# main.net
KiCad netlist of a schematic drawn in EAGLE
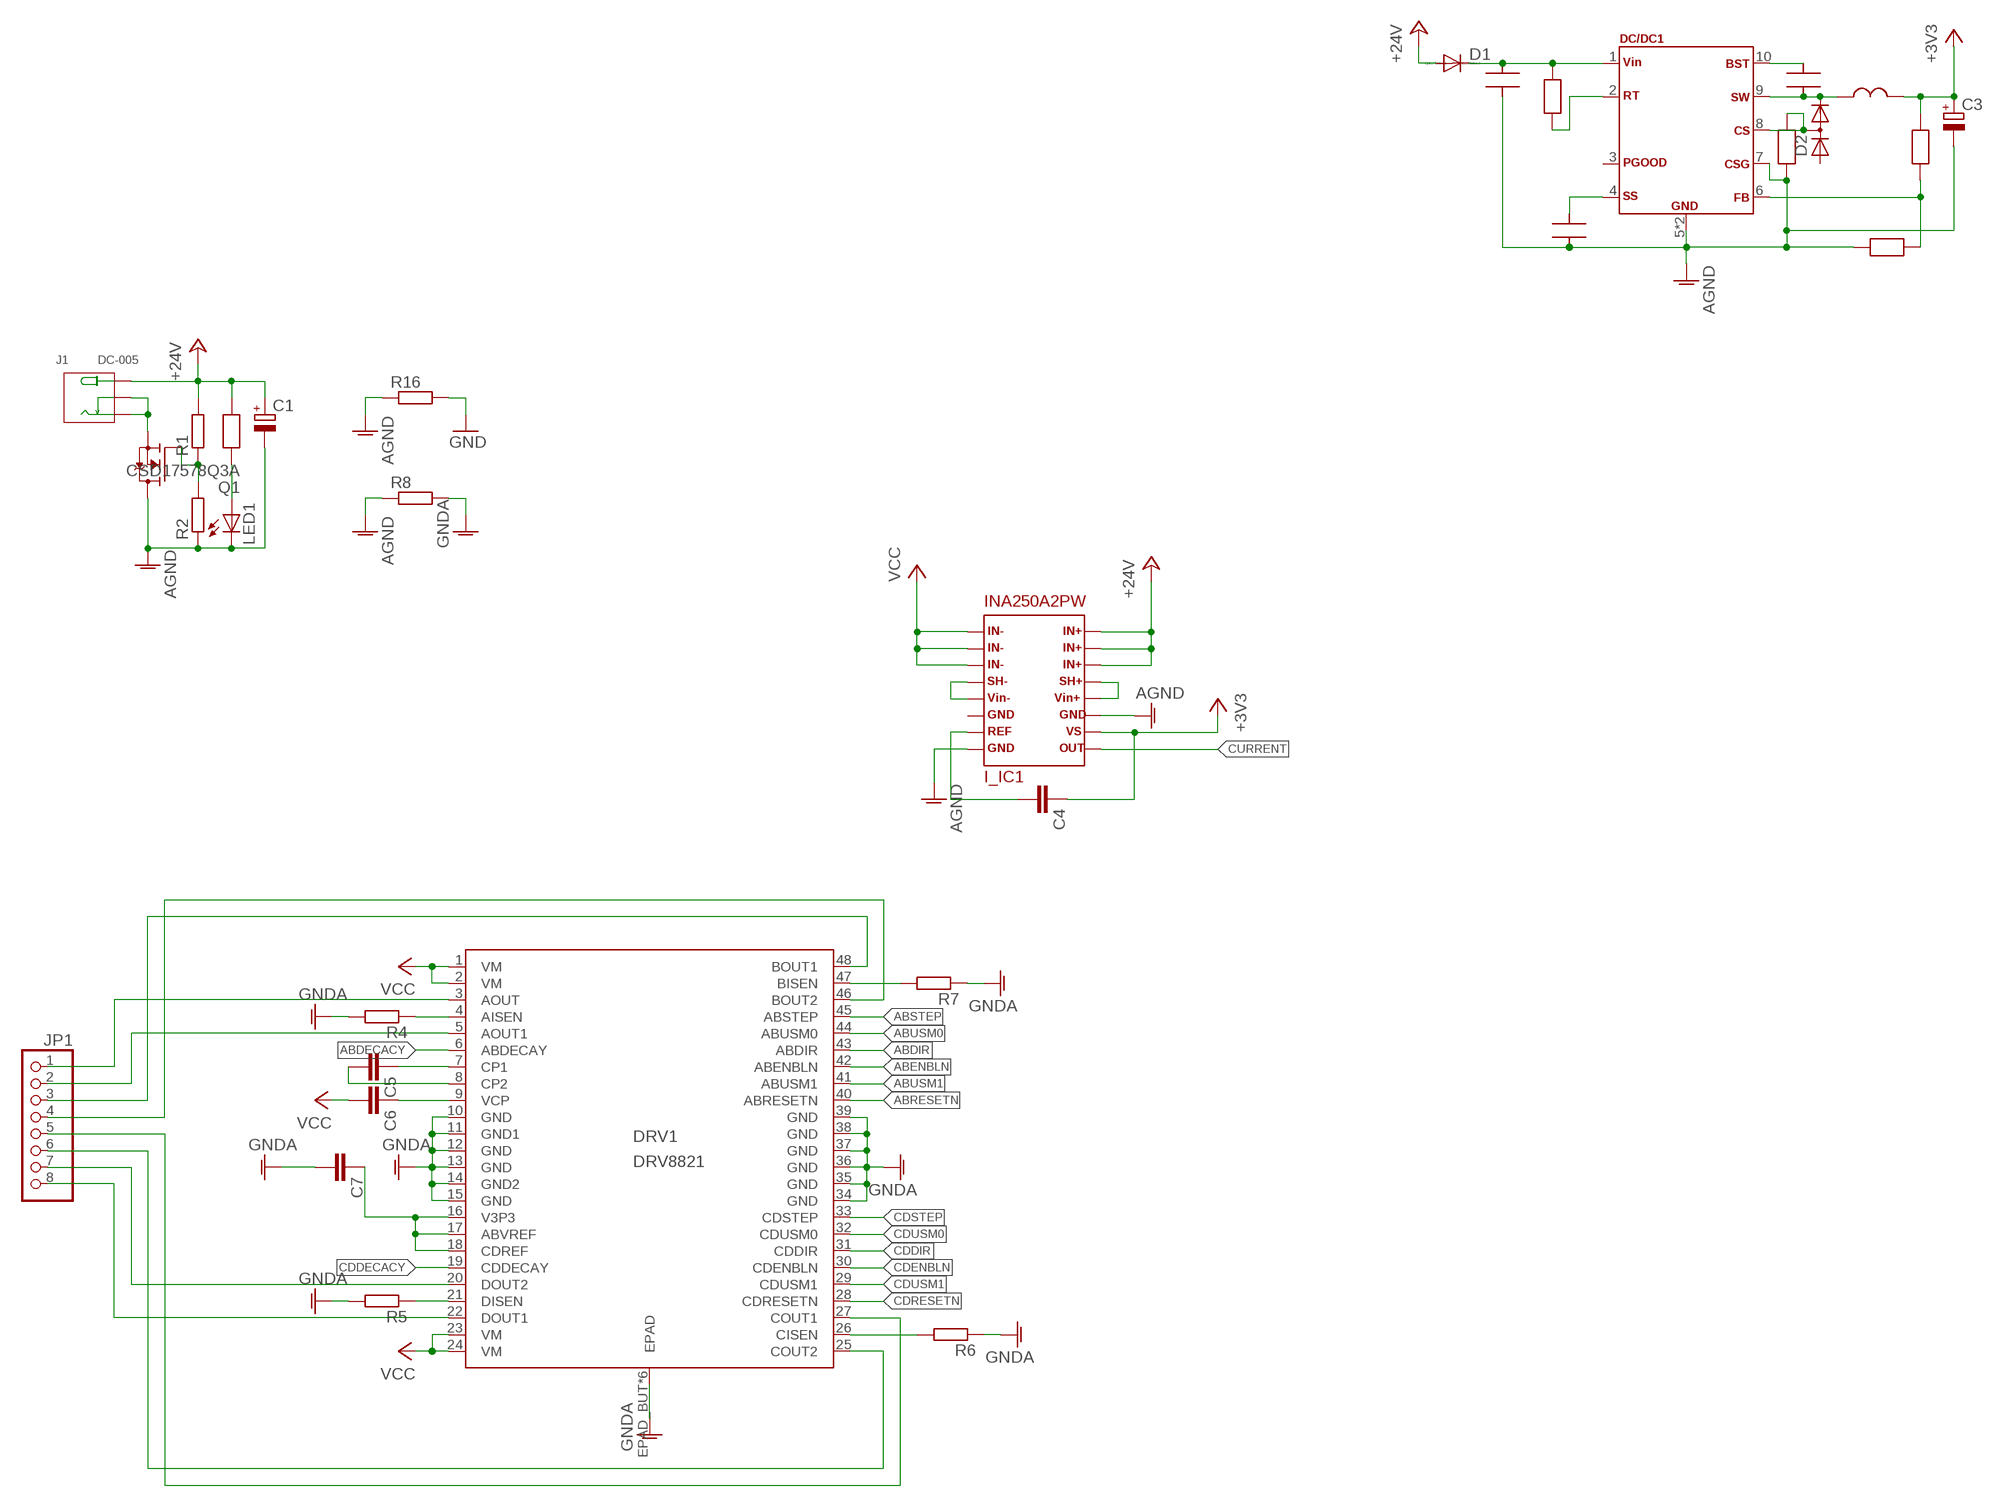
[diagram p0: schematic, sheet 1, part 1 of 2]
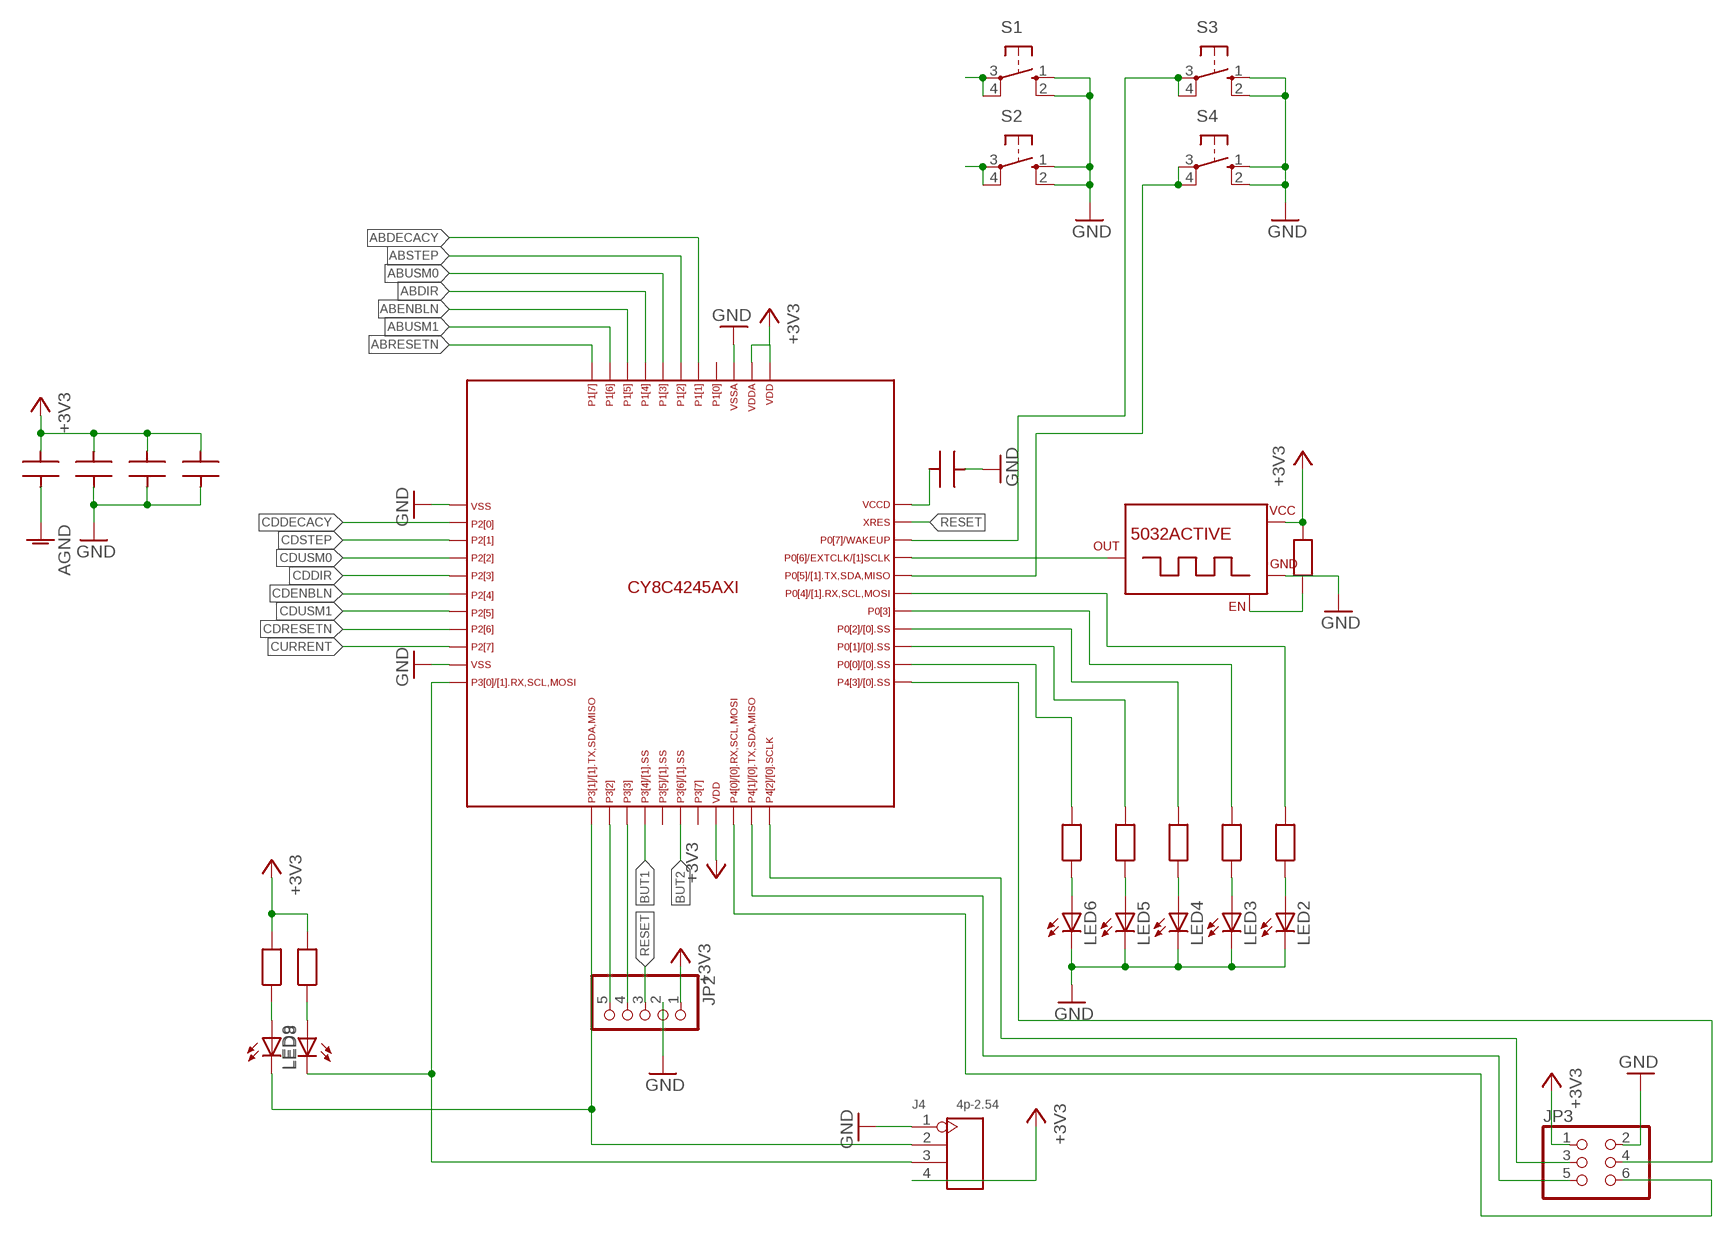
[diagram p1: schematic, sheet 1, part 2 of 2]

(export (version "E")
  (design (tool "Eeschema 10.0.6"))
  (components
    (comp (ref "C1")
      (value "CPOL-EUSMCD")
      (footprint "eagle-import:SMC_D")
      (libsource (lib "eagle-import") (part "CPOL-EUSMCD"))
    )
    (comp (ref "C2")
      (value "CAP0603")
      (footprint "eagle-import:C0603")
      (libsource (lib "eagle-import") (part "CAP0603"))
    )
    (comp (ref "C3")
      (value "CPOL-EUSMCD")
      (footprint "eagle-import:SMC_D")
      (libsource (lib "eagle-import") (part "CPOL-EUSMCD"))
    )
    (comp (ref "C4")
      (value "C-EUC0805")
      (footprint "eagle-import:C0805")
      (libsource (lib "eagle-import") (part "C-EUC0805"))
    )
    (comp (ref "C5")
      (value "C-EUC0805")
      (footprint "eagle-import:C0805")
      (libsource (lib "eagle-import") (part "C-EUC0805"))
    )
    (comp (ref "C6")
      (value "C-EUC0805")
      (footprint "eagle-import:C0805")
      (libsource (lib "eagle-import") (part "C-EUC0805"))
    )
    (comp (ref "C7")
      (value "C-EUC0805")
      (footprint "eagle-import:C0805")
      (libsource (lib "eagle-import") (part "C-EUC0805"))
    )
    (comp (ref "C8")
      (value "CAP0603")
      (footprint "eagle-import:C0603")
      (libsource (lib "eagle-import") (part "CAP0603"))
    )
    (comp (ref "C9")
      (value "CAP0603")
      (footprint "eagle-import:C0603")
      (libsource (lib "eagle-import") (part "CAP0603"))
    )
    (comp (ref "C10")
      (value "CAP0603")
      (footprint "eagle-import:C0603")
      (libsource (lib "eagle-import") (part "CAP0603"))
    )
    (comp (ref "C11")
      (value "CAP0603")
      (footprint "eagle-import:C0603")
      (libsource (lib "eagle-import") (part "CAP0603"))
    )
    (comp (ref "C12")
      (value "CAP0603")
      (footprint "eagle-import:C0603")
      (libsource (lib "eagle-import") (part "CAP0603"))
    )
    (comp (ref "C13")
      (value "CAP0603")
      (footprint "eagle-import:C0603")
      (libsource (lib "eagle-import") (part "CAP0603"))
    )
    (comp (ref "C14")
      (value "CAP0603")
      (footprint "eagle-import:C0603")
      (libsource (lib "eagle-import") (part "CAP0603"))
    )
    (comp (ref "D1")
      (value "DIODE-DO-214AC")
      (footprint "eagle-import:DO-214AC")
      (libsource (lib "eagle-import") (part "DIODE-DO-214AC"))
    )
    (comp (ref "D2")
      (value "DIODE_2CACA-SOT23")
      (footprint "eagle-import:SOT23")
      (libsource (lib "eagle-import") (part "DIODE_2CACA-SOT23"))
    )
    (comp (ref "DC/DC1")
      (value "LM25011")
      (footprint "eagle-import:HVSSOP-10")
      (libsource (lib "eagle-import") (part "LM25011"))
    )
    (comp (ref "DRV1")
      (value "DRV8821")
      (footprint "eagle-import:HTSSOP_48")
      (libsource (lib "eagle-import") (part "DRV8821"))
    )
    (comp (ref "I_IC1")
      (value "INA250A2PW")
      (footprint "eagle-import:SSOP16")
      (libsource (lib "eagle-import") (part "INA250A2PW"))
    )
    (comp (ref "J1")
      (value "DC-005")
      (footprint "eagle-import:DCJ3P-14.2X11.0X9.0MM")
      (libsource (lib "eagle-import") (part "CONN-POWER-JACK-2.1MM(DC-005)"))
    )
    (comp (ref "J4")
      (value "4p-2.54")
      (footprint "eagle-import:H4-2.54")
      (fields (field (name "MPN") "F185-1104A1BSYA1"))
      (libsource (lib "eagle-import") (part "DIP-BLACK-FEMALE-HEADER-VERT(4P-2.54)"))
    )
    (comp (ref "JP1")
      (value "PINHD-1X8")
      (footprint "eagle-import:1X08")
      (libsource (lib "eagle-import") (part "PINHD-1X8"))
    )
    (comp (ref "JP2")
      (value "PINHD-1X5")
      (footprint "eagle-import:1X05")
      (libsource (lib "eagle-import") (part "PINHD-1X5"))
    )
    (comp (ref "JP3")
      (value "PINHD-2X3")
      (footprint "eagle-import:2X03")
      (libsource (lib "eagle-import") (part "PINHD-2X3"))
    )
    (comp (ref "L1")
      (value "L0603")
      (footprint "eagle-import:L0603")
      (libsource (lib "eagle-import") (part "L0603"))
    )
    (comp (ref "LED1")
      (value "LEDCHIP-LED0805")
      (footprint "eagle-import:CHIP-LED0805")
      (libsource (lib "eagle-import") (part "LEDCHIP-LED0805"))
    )
    (comp (ref "LED2")
      (value "LEDCHIP-LED0603")
      (footprint "eagle-import:CHIP-LED0603")
      (libsource (lib "eagle-import") (part "LEDCHIP-LED0603"))
    )
    (comp (ref "LED3")
      (value "LEDCHIP-LED0603")
      (footprint "eagle-import:CHIP-LED0603")
      (libsource (lib "eagle-import") (part "LEDCHIP-LED0603"))
    )
    (comp (ref "LED4")
      (value "LEDCHIP-LED0603")
      (footprint "eagle-import:CHIP-LED0603")
      (libsource (lib "eagle-import") (part "LEDCHIP-LED0603"))
    )
    (comp (ref "LED5")
      (value "LEDCHIP-LED0603")
      (footprint "eagle-import:CHIP-LED0603")
      (libsource (lib "eagle-import") (part "LEDCHIP-LED0603"))
    )
    (comp (ref "LED6")
      (value "LEDCHIP-LED0603")
      (footprint "eagle-import:CHIP-LED0603")
      (libsource (lib "eagle-import") (part "LEDCHIP-LED0603"))
    )
    (comp (ref "LED8")
      (value "LEDCHIP-LED0603")
      (footprint "eagle-import:CHIP-LED0603")
      (libsource (lib "eagle-import") (part "LEDCHIP-LED0603"))
    )
    (comp (ref "LED9")
      (value "LEDCHIP-LED0603")
      (footprint "eagle-import:CHIP-LED0603")
      (libsource (lib "eagle-import") (part "LEDCHIP-LED0603"))
    )
    (comp (ref "Q1")
      (value "CSD17578Q3A")
      (footprint "eagle-import:VSONP8")
      (libsource (lib "eagle-import") (part "CSD17578Q3A"))
    )
    (comp (ref "R1")
      (value "R-EU_M0805")
      (footprint "eagle-import:M0805")
      (libsource (lib "eagle-import") (part "R-EU_M0805"))
    )
    (comp (ref "R2")
      (value "R-EU_M0805")
      (footprint "eagle-import:M0805")
      (libsource (lib "eagle-import") (part "R-EU_M0805"))
    )
    (comp (ref "R3")
      (value "RES0603")
      (footprint "eagle-import:R0603")
      (libsource (lib "eagle-import") (part "RES0603"))
    )
    (comp (ref "R4")
      (value "R-EU_M0805")
      (footprint "eagle-import:M0805")
      (libsource (lib "eagle-import") (part "R-EU_M0805"))
    )
    (comp (ref "R5")
      (value "R-EU_M0805")
      (footprint "eagle-import:M0805")
      (libsource (lib "eagle-import") (part "R-EU_M0805"))
    )
    (comp (ref "R6")
      (value "R-EU_M0805")
      (footprint "eagle-import:M0805")
      (libsource (lib "eagle-import") (part "R-EU_M0805"))
    )
    (comp (ref "R7")
      (value "R-EU_M0805")
      (footprint "eagle-import:M0805")
      (libsource (lib "eagle-import") (part "R-EU_M0805"))
    )
    (comp (ref "R8")
      (value "R-EU_M0805")
      (footprint "eagle-import:M0805")
      (libsource (lib "eagle-import") (part "R-EU_M0805"))
    )
    (comp (ref "R9")
      (value "RES0603")
      (footprint "eagle-import:R0603")
      (libsource (lib "eagle-import") (part "RES0603"))
    )
    (comp (ref "R10")
      (value "RES0603")
      (footprint "eagle-import:R0603")
      (libsource (lib "eagle-import") (part "RES0603"))
    )
    (comp (ref "R11")
      (value "RES0603")
      (footprint "eagle-import:R0603")
      (libsource (lib "eagle-import") (part "RES0603"))
    )
    (comp (ref "R12")
      (value "RES0603")
      (footprint "eagle-import:R0603")
      (libsource (lib "eagle-import") (part "RES0603"))
    )
    (comp (ref "R13")
      (value "RES0603")
      (footprint "eagle-import:R0603")
      (libsource (lib "eagle-import") (part "RES0603"))
    )
    (comp (ref "R14")
      (value "RES0603")
      (footprint "eagle-import:R0603")
      (libsource (lib "eagle-import") (part "RES0603"))
    )
    (comp (ref "R15")
      (value "RES0603")
      (footprint "eagle-import:R0603")
      (libsource (lib "eagle-import") (part "RES0603"))
    )
    (comp (ref "R16")
      (value "R-EU_M0805")
      (footprint "eagle-import:M0805")
      (libsource (lib "eagle-import") (part "R-EU_M0805"))
    )
    (comp (ref "R17")
      (value "RES0603")
      (footprint "eagle-import:R0603")
      (libsource (lib "eagle-import") (part "RES0603"))
    )
    (comp (ref "R18")
      (value "RES0603")
      (footprint "eagle-import:R0603")
      (libsource (lib "eagle-import") (part "RES0603"))
    )
    (comp (ref "R19")
      (value "RES0603")
      (footprint "eagle-import:R0603")
      (libsource (lib "eagle-import") (part "RES0603"))
    )
    (comp (ref "R20")
      (value "RES0603")
      (footprint "eagle-import:R0603")
      (libsource (lib "eagle-import") (part "RES0603"))
    )
    (comp (ref "R21")
      (value "RES0603")
      (footprint "eagle-import:R0603")
      (libsource (lib "eagle-import") (part "RES0603"))
    )
    (comp (ref "S1")
      (value "10-XX")
      (footprint "eagle-import:B3F-10XX")
      (fields (field (name "MPN") "B3F-1000"))
      (libsource (lib "eagle-import") (part "10-XX"))
    )
    (comp (ref "S2")
      (value "10-XX")
      (footprint "eagle-import:B3F-10XX")
      (fields (field (name "MPN") "B3F-1000"))
      (libsource (lib "eagle-import") (part "10-XX"))
    )
    (comp (ref "S3")
      (value "10-XX")
      (footprint "eagle-import:B3F-10XX")
      (fields (field (name "MPN") "B3F-1000"))
      (libsource (lib "eagle-import") (part "10-XX"))
    )
    (comp (ref "S4")
      (value "10-XX")
      (footprint "eagle-import:B3F-10XX")
      (fields (field (name "MPN") "B3F-1000"))
      (libsource (lib "eagle-import") (part "10-XX"))
    )
    (comp (ref "U$1")
      (value "CY8C4245")
      (footprint "eagle-import:TQFP44_CY_LOGO")
      (libsource (lib "eagle-import") (part "CY8C4245"))
    )
    (comp (ref "U$4")
      (value "5032ACTIVE")
      (footprint "eagle-import:5030A")
      (libsource (lib "eagle-import") (part "5032ACTIVE"))
    )
  )
  (nets
    (net (code "1") (name "+3V3") (class "Default")
      (node (ref "C10") (pin "1") (pinfunction "P$1_1") (pintype "bidirectional"))
      (node (ref "C12") (pin "1") (pinfunction "P$1_1") (pintype "bidirectional"))
      (node (ref "C13") (pin "1") (pinfunction "P$1_1") (pintype "bidirectional"))
      (node (ref "C14") (pin "1") (pinfunction "P$1_1") (pintype "bidirectional"))
      (node (ref "C3") (pin "+") (pinfunction "+_+") (pintype "passive"))
      (node (ref "C4") (pin "1") (pinfunction "1_1") (pintype "passive"))
      (node (ref "I_IC1") (pin "P$10") (pinfunction "P$10_P$10") (pintype "bidirectional"))
      (node (ref "J4") (pin "4") (pinfunction "P$4_4") (pintype "bidirectional"))
      (node (ref "JP2") (pin "1") (pinfunction "1_1") (pintype "passive"))
      (node (ref "JP3") (pin "1") (pinfunction "1_1") (pintype "passive"))
      (node (ref "L1") (pin "2") (pinfunction "P$2_2") (pintype "bidirectional"))
      (node (ref "R14") (pin "2") (pinfunction "P$2_2") (pintype "bidirectional"))
      (node (ref "R15") (pin "2") (pinfunction "P$2_2") (pintype "bidirectional"))
      (node (ref "R17") (pin "1") (pinfunction "P$1_1") (pintype "bidirectional"))
      (node (ref "R21") (pin "1") (pinfunction "P$1_1") (pintype "bidirectional"))
      (node (ref "U$1") (pin "19") (pinfunction "19_19") (pintype "bidirectional"))
      (node (ref "U$1") (pin "34") (pinfunction "34_34") (pintype "bidirectional"))
      (node (ref "U$1") (pin "35") (pinfunction "35_35") (pintype "bidirectional"))
      (node (ref "U$4") (pin "4") (pinfunction "+5V_4") (pintype "bidirectional"))
    )
    (net (code "2") (name "+24V") (class "Default")
      (node (ref "C1") (pin "+") (pinfunction "+_+") (pintype "passive"))
      (node (ref "D1") (pin "A") (pinfunction "A_A") (pintype "passive"))
      (node (ref "I_IC1") (pin "P$14") (pinfunction "P$14_P$14") (pintype "bidirectional"))
      (node (ref "I_IC1") (pin "P$15") (pinfunction "P$15_P$15") (pintype "bidirectional"))
      (node (ref "I_IC1") (pin "P$16") (pinfunction "P$16_P$16") (pintype "bidirectional"))
      (node (ref "J1") (pin "+") (pinfunction "+_+") (pintype "bidirectional"))
      (node (ref "R1") (pin "2") (pinfunction "2_2") (pintype "passive"))
      (node (ref "R3") (pin "2") (pinfunction "P$2_2") (pintype "bidirectional"))
    )
    (net (code "3") (name "ABDECACY") (class "Default")
      (node (ref "DRV1") (pin "6") (pinfunction "ABDECAY_6") (pintype "bidirectional"))
      (node (ref "U$1") (pin "38") (pinfunction "38_38") (pintype "bidirectional"))
    )
    (net (code "4") (name "ABDIR") (class "Default")
      (node (ref "DRV1") (pin "43") (pinfunction "ABDIR_43") (pintype "input"))
      (node (ref "U$1") (pin "41") (pinfunction "41_41") (pintype "bidirectional"))
    )
    (net (code "5") (name "ABENBLN") (class "Default")
      (node (ref "DRV1") (pin "42") (pinfunction "ABENBLN_42") (pintype "input"))
      (node (ref "U$1") (pin "42") (pinfunction "42_42") (pintype "bidirectional"))
    )
    (net (code "6") (name "ABRESETN") (class "Default")
      (node (ref "DRV1") (pin "40") (pinfunction "ABRESETN_40") (pintype "input"))
      (node (ref "U$1") (pin "44") (pinfunction "44_44") (pintype "bidirectional"))
    )
    (net (code "7") (name "ABSTEP") (class "Default")
      (node (ref "DRV1") (pin "45") (pinfunction "ABSTEP_45") (pintype "input"))
      (node (ref "U$1") (pin "39") (pinfunction "39_39") (pintype "bidirectional"))
    )
    (net (code "8") (name "ABUSM0") (class "Default")
      (node (ref "DRV1") (pin "44") (pinfunction "ABUSM0_44") (pintype "input"))
      (node (ref "U$1") (pin "40") (pinfunction "40_40") (pintype "bidirectional"))
    )
    (net (code "9") (name "ABUSM1") (class "Default")
      (node (ref "DRV1") (pin "41") (pinfunction "ABUSM1_41") (pintype "input"))
      (node (ref "U$1") (pin "43") (pinfunction "43_43") (pintype "bidirectional"))
    )
    (net (code "10") (name "AGND") (class "Default")
      (node (ref "C1") (pin "-") (pinfunction "-_-") (pintype "passive"))
      (node (ref "C14") (pin "2") (pinfunction "P$2_2") (pintype "bidirectional"))
      (node (ref "C2") (pin "1") (pinfunction "P$1_1") (pintype "bidirectional"))
      (node (ref "C3") (pin "-") (pinfunction "-_-") (pintype "passive"))
      (node (ref "C8") (pin "1") (pinfunction "P$1_1") (pintype "bidirectional"))
      (node (ref "DC/DC1") (pin "5") (pinfunction "5_5") (pintype "bidirectional"))
      (node (ref "DC/DC1") (pin "7") (pinfunction "7_7") (pintype "bidirectional"))
      (node (ref "DC/DC1") (pin "EPAD") (pinfunction "5_EPAD") (pintype "bidirectional"))
      (node (ref "I_IC1") (pin "P$11") (pinfunction "P$11_P$11") (pintype "bidirectional"))
      (node (ref "I_IC1") (pin "P$8") (pinfunction "P$8_P$8") (pintype "bidirectional"))
      (node (ref "LED1") (pin "C") (pinfunction "C_C") (pintype "passive"))
      (node (ref "Q1") (pin "D1") (pinfunction "D_D1") (pintype "passive"))
      (node (ref "Q1") (pin "D2") (pinfunction "D_D2") (pintype "passive"))
      (node (ref "Q1") (pin "D3") (pinfunction "D_D3") (pintype "passive"))
      (node (ref "Q1") (pin "D4") (pinfunction "D_D4") (pintype "passive"))
      (node (ref "Q1") (pin "D5") (pinfunction "D_D5") (pintype "passive"))
      (node (ref "R16") (pin "1") (pinfunction "1_1") (pintype "passive"))
      (node (ref "R19") (pin "1") (pinfunction "P$1_1") (pintype "bidirectional"))
      (node (ref "R2") (pin "1") (pinfunction "1_1") (pintype "passive"))
      (node (ref "R20") (pin "2") (pinfunction "P$2_2") (pintype "bidirectional"))
      (node (ref "R8") (pin "1") (pinfunction "1_1") (pintype "passive"))
    )
    (net (code "11") (name "BUT1") (class "Default")
      (node (ref "S1") (pin "3") (pinfunction "P_3") (pintype "passive"))
      (node (ref "S1") (pin "4") (pinfunction "P1_4") (pintype "passive"))
      (node (ref "U$1") (pin "15") (pinfunction "15_15") (pintype "bidirectional"))
    )
    (net (code "12") (name "BUT2") (class "Default")
      (node (ref "S2") (pin "3") (pinfunction "P_3") (pintype "passive"))
      (node (ref "S2") (pin "4") (pinfunction "P1_4") (pintype "passive"))
      (node (ref "U$1") (pin "17") (pinfunction "17_17") (pintype "bidirectional"))
    )
    (net (code "13") (name "CDDECACY") (class "Default")
      (node (ref "DRV1") (pin "19") (pinfunction "CDDECAY_19") (pintype "input"))
      (node (ref "U$1") (pin "2") (pinfunction "2_2") (pintype "bidirectional"))
    )
    (net (code "14") (name "CDDIR") (class "Default")
      (node (ref "DRV1") (pin "31") (pinfunction "CDDIR_31") (pintype "input"))
      (node (ref "U$1") (pin "5") (pinfunction "5_5") (pintype "bidirectional"))
    )
    (net (code "15") (name "CDENBLN") (class "Default")
      (node (ref "DRV1") (pin "30") (pinfunction "CDENBLN_30") (pintype "input"))
      (node (ref "U$1") (pin "6") (pinfunction "6_6") (pintype "bidirectional"))
    )
    (net (code "16") (name "CDRESETN") (class "Default")
      (node (ref "DRV1") (pin "28") (pinfunction "CDRESETN_28") (pintype "input"))
      (node (ref "U$1") (pin "8") (pinfunction "8_8") (pintype "bidirectional"))
    )
    (net (code "17") (name "CDSTEP") (class "Default")
      (node (ref "DRV1") (pin "33") (pinfunction "CDSTEP_33") (pintype "input"))
      (node (ref "U$1") (pin "3") (pinfunction "3_3") (pintype "bidirectional"))
    )
    (net (code "18") (name "CDUSM0") (class "Default")
      (node (ref "DRV1") (pin "32") (pinfunction "CDUSM0_32") (pintype "input"))
      (node (ref "U$1") (pin "4") (pinfunction "4_4") (pintype "bidirectional"))
    )
    (net (code "19") (name "CDUSM1") (class "Default")
      (node (ref "DRV1") (pin "29") (pinfunction "CDUSM1_29") (pintype "input"))
      (node (ref "U$1") (pin "7") (pinfunction "7_7") (pintype "bidirectional"))
    )
    (net (code "20") (name "CURRENT") (class "Default")
      (node (ref "I_IC1") (pin "P$9") (pinfunction "P$9_P$9") (pintype "bidirectional"))
      (node (ref "U$1") (pin "9") (pinfunction "9_9") (pintype "bidirectional"))
    )
    (net (code "21") (name "GND") (class "Default")
      (node (ref "C10") (pin "2") (pinfunction "P$2_2") (pintype "bidirectional"))
      (node (ref "C11") (pin "1") (pinfunction "P$1_1") (pintype "bidirectional"))
      (node (ref "C12") (pin "2") (pinfunction "P$2_2") (pintype "bidirectional"))
      (node (ref "C13") (pin "2") (pinfunction "P$2_2") (pintype "bidirectional"))
      (node (ref "J4") (pin "1") (pinfunction "P$1_1") (pintype "bidirectional"))
      (node (ref "JP2") (pin "2") (pinfunction "2_2") (pintype "passive"))
      (node (ref "JP3") (pin "2") (pinfunction "2_2") (pintype "passive"))
      (node (ref "LED2") (pin "C") (pinfunction "C_C") (pintype "passive"))
      (node (ref "LED3") (pin "C") (pinfunction "C_C") (pintype "passive"))
      (node (ref "LED4") (pin "C") (pinfunction "C_C") (pintype "passive"))
      (node (ref "LED5") (pin "C") (pinfunction "C_C") (pintype "passive"))
      (node (ref "LED6") (pin "C") (pinfunction "C_C") (pintype "passive"))
      (node (ref "R16") (pin "2") (pinfunction "2_2") (pintype "passive"))
      (node (ref "S1") (pin "1") (pinfunction "S_1") (pintype "passive"))
      (node (ref "S1") (pin "2") (pinfunction "S1_2") (pintype "passive"))
      (node (ref "S2") (pin "1") (pinfunction "S_1") (pintype "passive"))
      (node (ref "S2") (pin "2") (pinfunction "S1_2") (pintype "passive"))
      (node (ref "S3") (pin "1") (pinfunction "S_1") (pintype "passive"))
      (node (ref "S3") (pin "2") (pinfunction "S1_2") (pintype "passive"))
      (node (ref "S4") (pin "1") (pinfunction "S_1") (pintype "passive"))
      (node (ref "S4") (pin "2") (pinfunction "S1_2") (pintype "passive"))
      (node (ref "U$1") (pin "1") (pinfunction "1_1") (pintype "bidirectional"))
      (node (ref "U$1") (pin "10") (pinfunction "10_10") (pintype "bidirectional"))
      (node (ref "U$1") (pin "36") (pinfunction "36_36") (pintype "bidirectional"))
      (node (ref "U$4") (pin "2") (pinfunction "GND_2") (pintype "bidirectional"))
    )
    (net (code "22") (name "GNDA") (class "Default")
      (node (ref "C7") (pin "2") (pinfunction "2_2") (pintype "passive"))
      (node (ref "DRV1") (pin "10") (pinfunction "GND_10") (pintype "power_in"))
      (node (ref "DRV1") (pin "11") (pinfunction "GND1_11") (pintype "power_in"))
      (node (ref "DRV1") (pin "12") (pinfunction "GND_12") (pintype "power_in"))
      (node (ref "DRV1") (pin "13") (pinfunction "GND_13") (pintype "power_in"))
      (node (ref "DRV1") (pin "14") (pinfunction "GND2_14") (pintype "power_in"))
      (node (ref "DRV1") (pin "15") (pinfunction "GND_15") (pintype "power_in"))
      (node (ref "DRV1") (pin "34") (pinfunction "GND_34") (pintype "power_in"))
      (node (ref "DRV1") (pin "35") (pinfunction "GND_35") (pintype "power_in"))
      (node (ref "DRV1") (pin "36") (pinfunction "GND_36") (pintype "power_in"))
      (node (ref "DRV1") (pin "37") (pinfunction "GND_37") (pintype "power_in"))
      (node (ref "DRV1") (pin "38") (pinfunction "GND_38") (pintype "power_in"))
      (node (ref "DRV1") (pin "39") (pinfunction "GND_39") (pintype "power_in"))
      (node (ref "DRV1") (pin "EPAD_BUT") (pinfunction "EPAD_EPAD_BUT") (pintype "power_in"))
      (node (ref "DRV1") (pin "EPAD_TOP") (pinfunction "EPAD_EPAD_TOP") (pintype "power_in"))
      (node (ref "DRV1") (pin "EPAD_VIA1") (pinfunction "EPAD_EPAD_VIA1") (pintype "power_in"))
      (node (ref "DRV1") (pin "EPAD_VIA2") (pinfunction "EPAD_EPAD_VIA2") (pintype "power_in"))
      (node (ref "DRV1") (pin "EPAD_VIA3") (pinfunction "EPAD_EPAD_VIA3") (pintype "power_in"))
      (node (ref "DRV1") (pin "EPAD_VIA4") (pinfunction "EPAD_EPAD_VIA4") (pintype "power_in"))
      (node (ref "R4") (pin "2") (pinfunction "2_2") (pintype "passive"))
      (node (ref "R5") (pin "2") (pinfunction "2_2") (pintype "passive"))
      (node (ref "R6") (pin "1") (pinfunction "1_1") (pintype "passive"))
      (node (ref "R7") (pin "1") (pinfunction "1_1") (pintype "passive"))
      (node (ref "R8") (pin "2") (pinfunction "2_2") (pintype "passive"))
    )
    (net (code "23") (name "Net-(C2-P$2)") (class "Default")
      (node (ref "C2") (pin "2") (pinfunction "P$2_2") (pintype "bidirectional"))
      (node (ref "D1") (pin "C") (pinfunction "C_C") (pintype "passive"))
      (node (ref "DC/DC1") (pin "1") (pinfunction "1_1") (pintype "bidirectional"))
      (node (ref "R18") (pin "2") (pinfunction "P$2_2") (pintype "bidirectional"))
    )
    (net (code "24") (name "Net-(C4-Pad2)") (class "Default")
      (node (ref "C4") (pin "2") (pinfunction "2_2") (pintype "passive"))
      (node (ref "I_IC1") (pin "P$7") (pinfunction "P$7_P$7") (pintype "bidirectional"))
    )
    (net (code "25") (name "Net-(C8-P$2)") (class "Default")
      (node (ref "C8") (pin "2") (pinfunction "P$2_2") (pintype "bidirectional"))
      (node (ref "DC/DC1") (pin "4") (pinfunction "4_4") (pintype "bidirectional"))
    )
    (net (code "26") (name "Net-(C9-P$1)") (class "Default")
      (node (ref "C9") (pin "1") (pinfunction "P$1_1") (pintype "bidirectional"))
      (node (ref "D2") (pin "2") (pinfunction "C_2") (pintype "passive"))
      (node (ref "DC/DC1") (pin "9") (pinfunction "9_9") (pintype "bidirectional"))
      (node (ref "L1") (pin "1") (pinfunction "P$1_1") (pintype "bidirectional"))
    )
    (net (code "27") (name "Net-(C9-P$2)") (class "Default")
      (node (ref "C9") (pin "2") (pinfunction "P$2_2") (pintype "bidirectional"))
      (node (ref "DC/DC1") (pin "10") (pinfunction "10_10") (pintype "bidirectional"))
    )
    (net (code "28") (name "Net-(C11-P$2)") (class "Default")
      (node (ref "C11") (pin "2") (pinfunction "P$2_2") (pintype "bidirectional"))
      (node (ref "U$1") (pin "33") (pinfunction "33_33") (pintype "bidirectional"))
    )
    (net (code "29") (name "Net-(D2-AC)") (class "Default")
      (node (ref "D2") (pin "3") (pinfunction "AC_3") (pintype "passive"))
      (node (ref "DC/DC1") (pin "8") (pinfunction "8_8") (pintype "bidirectional"))
      (node (ref "R19") (pin "2") (pinfunction "P$2_2") (pintype "bidirectional"))
    )
    (net (code "30") (name "Net-(DRV1-ABVREF)") (class "Default")
      (node (ref "C7") (pin "1") (pinfunction "1_1") (pintype "passive"))
      (node (ref "DRV1") (pin "16") (pinfunction "V3P3_16") (pintype "output"))
      (node (ref "DRV1") (pin "17") (pinfunction "ABVREF_17") (pintype "input"))
      (node (ref "DRV1") (pin "18") (pinfunction "CDREF_18") (pintype "input"))
    )
    (net (code "31") (name "Net-(DRV1-AISEN)") (class "Default")
      (node (ref "DRV1") (pin "4") (pinfunction "AISEN_4") (pintype "bidirectional"))
      (node (ref "R4") (pin "1") (pinfunction "1_1") (pintype "passive"))
    )
    (net (code "32") (name "Net-(DRV1-AOUT)") (class "Default")
      (node (ref "DRV1") (pin "3") (pinfunction "AOUT_3") (pintype "output"))
      (node (ref "JP1") (pin "1") (pinfunction "1_1") (pintype "passive"))
    )
    (net (code "33") (name "Net-(DRV1-AOUT1)") (class "Default")
      (node (ref "DRV1") (pin "5") (pinfunction "AOUT1_5") (pintype "output"))
      (node (ref "JP1") (pin "2") (pinfunction "2_2") (pintype "passive"))
    )
    (net (code "34") (name "Net-(DRV1-BISEN)") (class "Default")
      (node (ref "DRV1") (pin "47") (pinfunction "BISEN_47") (pintype "bidirectional"))
      (node (ref "R7") (pin "2") (pinfunction "2_2") (pintype "passive"))
    )
    (net (code "35") (name "Net-(DRV1-BOUT1)") (class "Default")
      (node (ref "DRV1") (pin "48") (pinfunction "BOUT1_48") (pintype "output"))
      (node (ref "JP1") (pin "3") (pinfunction "3_3") (pintype "passive"))
    )
    (net (code "36") (name "Net-(DRV1-BOUT2)") (class "Default")
      (node (ref "DRV1") (pin "46") (pinfunction "BOUT2_46") (pintype "output"))
      (node (ref "JP1") (pin "4") (pinfunction "4_4") (pintype "passive"))
    )
    (net (code "37") (name "Net-(DRV1-CISEN)") (class "Default")
      (node (ref "DRV1") (pin "26") (pinfunction "CISEN_26") (pintype "bidirectional"))
      (node (ref "R6") (pin "2") (pinfunction "2_2") (pintype "passive"))
    )
    (net (code "38") (name "Net-(DRV1-COUT1)") (class "Default")
      (node (ref "DRV1") (pin "27") (pinfunction "COUT1_27") (pintype "output"))
      (node (ref "JP1") (pin "5") (pinfunction "5_5") (pintype "passive"))
    )
    (net (code "39") (name "Net-(DRV1-COUT2)") (class "Default")
      (node (ref "DRV1") (pin "25") (pinfunction "COUT2_25") (pintype "output"))
      (node (ref "JP1") (pin "6") (pinfunction "6_6") (pintype "passive"))
    )
    (net (code "40") (name "Net-(DRV1-CP1)") (class "Default")
      (node (ref "C5") (pin "1") (pinfunction "1_1") (pintype "passive"))
      (node (ref "DRV1") (pin "7") (pinfunction "CP1_7") (pintype "bidirectional"))
    )
    (net (code "41") (name "Net-(DRV1-CP2)") (class "Default")
      (node (ref "C5") (pin "2") (pinfunction "2_2") (pintype "passive"))
      (node (ref "DRV1") (pin "8") (pinfunction "CP2_8") (pintype "bidirectional"))
    )
    (net (code "42") (name "Net-(DRV1-DISEN)") (class "Default")
      (node (ref "DRV1") (pin "21") (pinfunction "DISEN_21") (pintype "bidirectional"))
      (node (ref "R5") (pin "1") (pinfunction "1_1") (pintype "passive"))
    )
    (net (code "43") (name "Net-(DRV1-DOUT1)") (class "Default")
      (node (ref "DRV1") (pin "22") (pinfunction "DOUT1_22") (pintype "output"))
      (node (ref "JP1") (pin "8") (pinfunction "8_8") (pintype "passive"))
    )
    (net (code "44") (name "Net-(DRV1-DOUT2)") (class "Default")
      (node (ref "DRV1") (pin "20") (pinfunction "DOUT2_20") (pintype "output"))
      (node (ref "JP1") (pin "7") (pinfunction "7_7") (pintype "passive"))
    )
    (net (code "45") (name "Net-(DRV1-VCP)") (class "Default")
      (node (ref "C6") (pin "1") (pinfunction "1_1") (pintype "passive"))
      (node (ref "DRV1") (pin "9") (pinfunction "VCP_9") (pintype "bidirectional"))
    )
    (net (code "46") (name "Net-(I_IC1-PadP$4)") (class "Default")
      (node (ref "I_IC1") (pin "P$4") (pinfunction "P$4_P$4") (pintype "bidirectional"))
      (node (ref "I_IC1") (pin "P$5") (pinfunction "P$5_P$5") (pintype "bidirectional"))
    )
    (net (code "47") (name "Net-(I_IC1-PadP$12)") (class "Default")
      (node (ref "I_IC1") (pin "P$12") (pinfunction "P$12_P$12") (pintype "bidirectional"))
      (node (ref "I_IC1") (pin "P$13") (pinfunction "P$13_P$13") (pintype "bidirectional"))
    )
    (net (code "48") (name "Net-(J1--)") (class "Default")
      (node (ref "J1") (pin "-1") (pinfunction "-_-1") (pintype "bidirectional"))
      (node (ref "J1") (pin "-2") (pinfunction "CDN_-2") (pintype "bidirectional"))
      (node (ref "Q1") (pin "S1") (pinfunction "S_S1") (pintype "passive"))
      (node (ref "Q1") (pin "S2") (pinfunction "S_S2") (pintype "passive"))
      (node (ref "Q1") (pin "S3") (pinfunction "S_S3") (pintype "passive"))
    )
    (net (code "49") (name "Net-(J4-P$2)") (class "Default")
      (node (ref "J4") (pin "2") (pinfunction "P$2_2") (pintype "bidirectional"))
      (node (ref "LED8") (pin "C") (pinfunction "C_C") (pintype "passive"))
      (node (ref "U$1") (pin "12") (pinfunction "12_12") (pintype "bidirectional"))
    )
    (net (code "50") (name "Net-(J4-P$3)") (class "Default")
      (node (ref "J4") (pin "3") (pinfunction "P$3_3") (pintype "bidirectional"))
      (node (ref "LED9") (pin "C") (pinfunction "C_C") (pintype "passive"))
      (node (ref "U$1") (pin "11") (pinfunction "11_11") (pintype "bidirectional"))
    )
    (net (code "51") (name "Net-(JP2-Pad4)") (class "Default")
      (node (ref "JP2") (pin "4") (pinfunction "4_4") (pintype "passive"))
      (node (ref "U$1") (pin "14") (pinfunction "14_14") (pintype "bidirectional"))
    )
    (net (code "52") (name "Net-(JP2-Pad5)") (class "Default")
      (node (ref "JP2") (pin "5") (pinfunction "5_5") (pintype "passive"))
      (node (ref "U$1") (pin "13") (pinfunction "13_13") (pintype "bidirectional"))
    )
    (net (code "53") (name "Net-(JP3-Pad3)") (class "Default")
      (node (ref "JP3") (pin "3") (pinfunction "3_3") (pintype "passive"))
      (node (ref "U$1") (pin "22") (pinfunction "22_22") (pintype "bidirectional"))
    )
    (net (code "54") (name "Net-(JP3-Pad4)") (class "Default")
      (node (ref "JP3") (pin "4") (pinfunction "4_4") (pintype "passive"))
      (node (ref "U$1") (pin "23") (pinfunction "23_23") (pintype "bidirectional"))
    )
    (net (code "55") (name "Net-(JP3-Pad5)") (class "Default")
      (node (ref "JP3") (pin "5") (pinfunction "5_5") (pintype "passive"))
      (node (ref "U$1") (pin "21") (pinfunction "21_21") (pintype "bidirectional"))
    )
    (net (code "56") (name "Net-(JP3-Pad6)") (class "Default")
      (node (ref "JP3") (pin "6") (pinfunction "6_6") (pintype "passive"))
      (node (ref "U$1") (pin "20") (pinfunction "20_20") (pintype "bidirectional"))
    )
    (net (code "57") (name "Net-(Q1-PadG)") (class "Default")
      (node (ref "Q1") (pin "G") (pinfunction "G_G") (pintype "passive"))
      (node (ref "R1") (pin "1") (pinfunction "1_1") (pintype "passive"))
      (node (ref "R2") (pin "2") (pinfunction "2_2") (pintype "passive"))
    )
    (net (code "58") (name "Net-(R3-P$1)") (class "Default")
      (node (ref "LED1") (pin "A") (pinfunction "A_A") (pintype "passive"))
      (node (ref "R3") (pin "1") (pinfunction "P$1_1") (pintype "bidirectional"))
    )
    (net (code "59") (name "Net-(R9-P$1)") (class "Default")
      (node (ref "LED6") (pin "A") (pinfunction "A_A") (pintype "passive"))
      (node (ref "R9") (pin "1") (pinfunction "P$1_1") (pintype "bidirectional"))
    )
    (net (code "60") (name "Net-(R9-P$2)") (class "Default")
      (node (ref "R9") (pin "2") (pinfunction "P$2_2") (pintype "bidirectional"))
      (node (ref "U$1") (pin "24") (pinfunction "24_24") (pintype "bidirectional"))
    )
    (net (code "61") (name "Net-(R10-P$1)") (class "Default")
      (node (ref "LED5") (pin "A") (pinfunction "A_A") (pintype "passive"))
      (node (ref "R10") (pin "1") (pinfunction "P$1_1") (pintype "bidirectional"))
    )
    (net (code "62") (name "Net-(R10-P$2)") (class "Default")
      (node (ref "R10") (pin "2") (pinfunction "P$2_2") (pintype "bidirectional"))
      (node (ref "U$1") (pin "25") (pinfunction "25_25") (pintype "bidirectional"))
    )
    (net (code "63") (name "Net-(R11-P$1)") (class "Default")
      (node (ref "LED4") (pin "A") (pinfunction "A_A") (pintype "passive"))
      (node (ref "R11") (pin "1") (pinfunction "P$1_1") (pintype "bidirectional"))
    )
    (net (code "64") (name "Net-(R11-P$2)") (class "Default")
      (node (ref "R11") (pin "2") (pinfunction "P$2_2") (pintype "bidirectional"))
      (node (ref "U$1") (pin "26") (pinfunction "26_26") (pintype "bidirectional"))
    )
    (net (code "65") (name "Net-(R12-P$1)") (class "Default")
      (node (ref "LED3") (pin "A") (pinfunction "A_A") (pintype "passive"))
      (node (ref "R12") (pin "1") (pinfunction "P$1_1") (pintype "bidirectional"))
    )
    (net (code "66") (name "Net-(R12-P$2)") (class "Default")
      (node (ref "R12") (pin "2") (pinfunction "P$2_2") (pintype "bidirectional"))
      (node (ref "U$1") (pin "27") (pinfunction "27_27") (pintype "bidirectional"))
    )
    (net (code "67") (name "Net-(R13-P$1)") (class "Default")
      (node (ref "LED2") (pin "A") (pinfunction "A_A") (pintype "passive"))
      (node (ref "R13") (pin "1") (pinfunction "P$1_1") (pintype "bidirectional"))
    )
    (net (code "68") (name "Net-(R13-P$2)") (class "Default")
      (node (ref "R13") (pin "2") (pinfunction "P$2_2") (pintype "bidirectional"))
      (node (ref "U$1") (pin "28") (pinfunction "28_28") (pintype "bidirectional"))
    )
    (net (code "69") (name "Net-(R14-P$1)") (class "Default")
      (node (ref "LED8") (pin "A") (pinfunction "A_A") (pintype "passive"))
      (node (ref "R14") (pin "1") (pinfunction "P$1_1") (pintype "bidirectional"))
    )
    (net (code "70") (name "Net-(R15-P$1)") (class "Default")
      (node (ref "LED9") (pin "A") (pinfunction "A_A") (pintype "passive"))
      (node (ref "R15") (pin "1") (pinfunction "P$1_1") (pintype "bidirectional"))
    )
    (net (code "71") (name "Net-(R17-P$2)") (class "Default")
      (node (ref "R17") (pin "2") (pinfunction "P$2_2") (pintype "bidirectional"))
      (node (ref "U$4") (pin "1") (pinfunction "EN_1") (pintype "bidirectional"))
    )
    (net (code "72") (name "Net-(R18-P$1)") (class "Default")
      (node (ref "DC/DC1") (pin "2") (pinfunction "2_2") (pintype "bidirectional"))
      (node (ref "R18") (pin "1") (pinfunction "P$1_1") (pintype "bidirectional"))
    )
    (net (code "73") (name "Net-(R20-P$1)") (class "Default")
      (node (ref "DC/DC1") (pin "6") (pinfunction "6_6") (pintype "bidirectional"))
      (node (ref "R20") (pin "1") (pinfunction "P$1_1") (pintype "bidirectional"))
      (node (ref "R21") (pin "2") (pinfunction "P$2_2") (pintype "bidirectional"))
    )
    (net (code "74") (name "Net-(S3-P)") (class "Default")
      (node (ref "S3") (pin "3") (pinfunction "P_3") (pintype "passive"))
      (node (ref "S3") (pin "4") (pinfunction "P1_4") (pintype "passive"))
      (node (ref "U$1") (pin "31") (pinfunction "31_31") (pintype "bidirectional"))
    )
    (net (code "75") (name "Net-(S4-P)") (class "Default")
      (node (ref "S4") (pin "3") (pinfunction "P_3") (pintype "passive"))
      (node (ref "S4") (pin "4") (pinfunction "P1_4") (pintype "passive"))
      (node (ref "U$1") (pin "29") (pinfunction "29_29") (pintype "bidirectional"))
    )
    (net (code "76") (name "Net-(U$4-OUT)") (class "Default")
      (node (ref "U$1") (pin "30") (pinfunction "30_30") (pintype "bidirectional"))
      (node (ref "U$4") (pin "3") (pinfunction "OUT_3") (pintype "bidirectional"))
    )
    (net (code "77") (name "RESET") (class "Default")
      (node (ref "JP2") (pin "3") (pinfunction "3_3") (pintype "passive"))
      (node (ref "U$1") (pin "32") (pinfunction "32_32") (pintype "bidirectional"))
    )
    (net (code "78") (name "VCC") (class "Default")
      (node (ref "C6") (pin "2") (pinfunction "2_2") (pintype "passive"))
      (node (ref "DRV1") (pin "1") (pinfunction "VM_1") (pintype "power_in"))
      (node (ref "DRV1") (pin "2") (pinfunction "VM_2") (pintype "power_in"))
      (node (ref "DRV1") (pin "23") (pinfunction "VM_23") (pintype "power_in"))
      (node (ref "DRV1") (pin "24") (pinfunction "VM_24") (pintype "power_in"))
      (node (ref "I_IC1") (pin "P$1") (pinfunction "P$1_P$1") (pintype "bidirectional"))
      (node (ref "I_IC1") (pin "P$2") (pinfunction "P$2_P$2") (pintype "bidirectional"))
      (node (ref "I_IC1") (pin "P$3") (pinfunction "P$3_P$3") (pintype "bidirectional"))
    )
    (net (code "79") (name "unconnected-(D2-A-Pad1)") (class "Default")
      (node (ref "D2") (pin "1") (pinfunction "A_1") (pintype "passive"))
    )
    (net (code "80") (name "unconnected-(DC/DC1-Pad3)") (class "Default")
      (node (ref "DC/DC1") (pin "3") (pinfunction "3_3") (pintype "bidirectional"))
    )
    (net (code "81") (name "unconnected-(I_IC1-PadP$6)") (class "Default")
      (node (ref "I_IC1") (pin "P$6") (pinfunction "P$6_P$6") (pintype "bidirectional"))
    )
    (net (code "82") (name "unconnected-(U$1-Pad16)") (class "Default")
      (node (ref "U$1") (pin "16") (pinfunction "16_16") (pintype "bidirectional"))
    )
    (net (code "83") (name "unconnected-(U$1-Pad18)") (class "Default")
      (node (ref "U$1") (pin "18") (pinfunction "18_18") (pintype "bidirectional"))
    )
    (net (code "84") (name "unconnected-(U$1-Pad37)") (class "Default")
      (node (ref "U$1") (pin "37") (pinfunction "37_37") (pintype "bidirectional"))
    )
  )
)
